# SoM-MGTH.net
KiCad netlist of a schematic drawn in Altium Designer
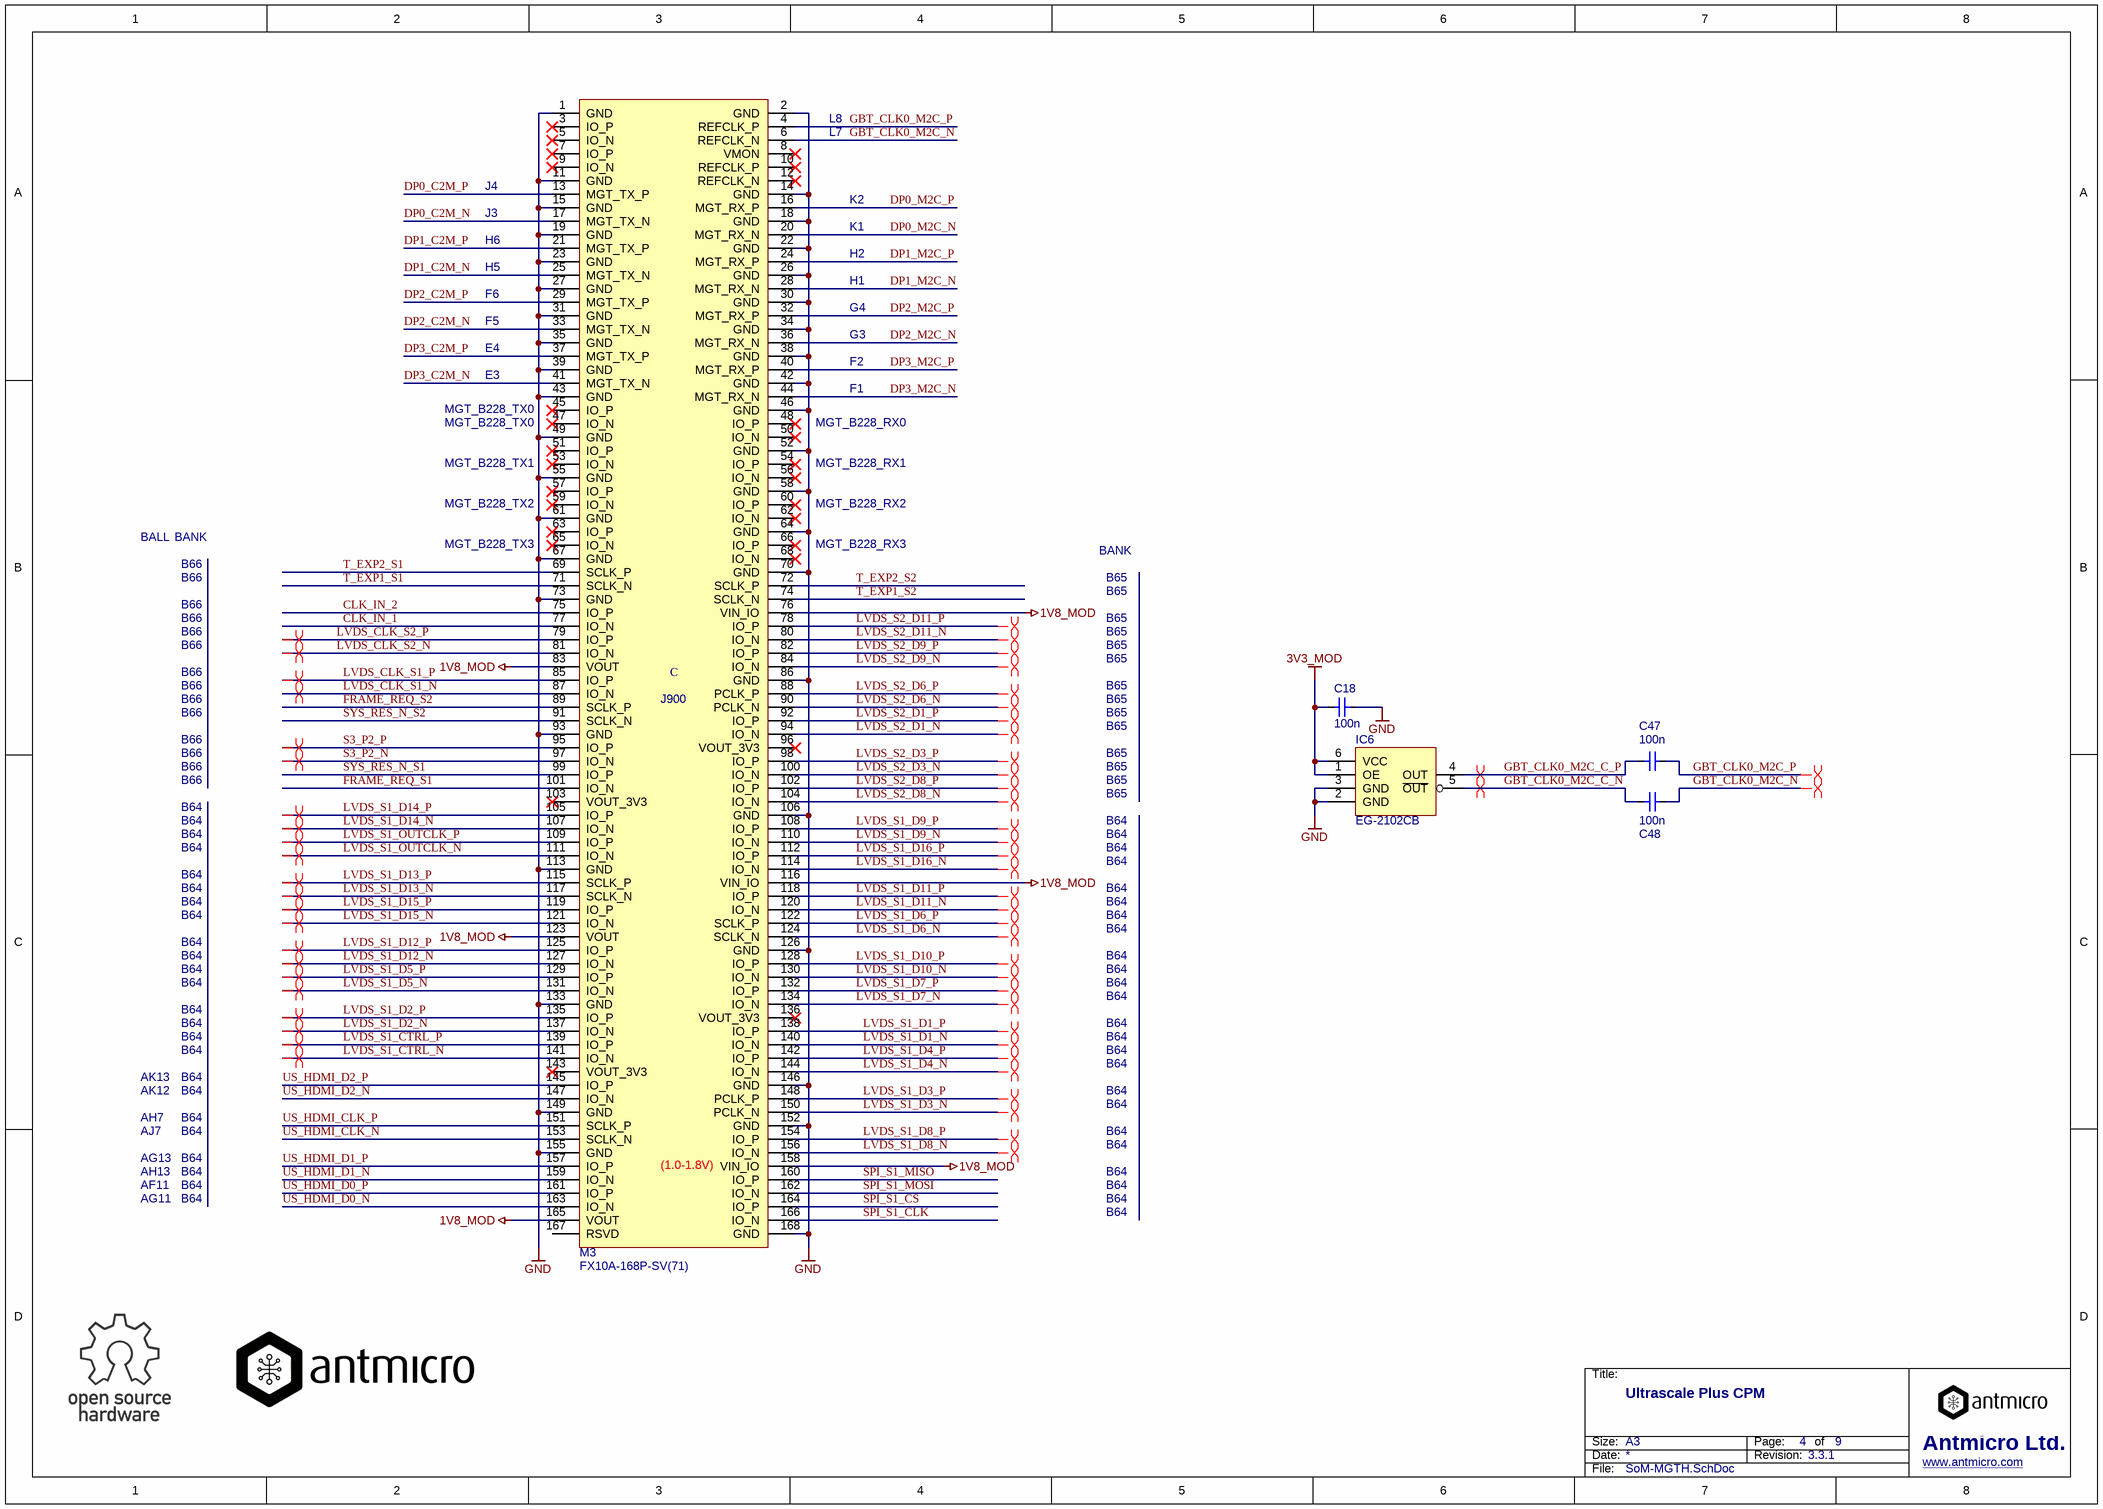
[diagram p0: SoM-MGTH.SchDoc]

(export (version "E")
  (design (tool "Eeschema 10.0.6"))
  (components
    (comp (ref "C18")
      (value "100n")
      (footprint "0402")
      (description "MLCC SMT Capacitor 100nF 0402")
      (fields (field (name "PART NUMBER") "C_100n_0402") (field (name "MANUFACTURER") "MULTICOMP"))
      (libsource (lib "US-Plus-CPM") (part "C"))
    )
    (comp (ref "C47")
      (value "100n")
      (footprint "0402")
      (description "MLCC SMT Capacitor 100nF 0402")
      (fields (field (name "PART NUMBER") "C_100n_0402") (field (name "MANUFACTURER") "MULTICOMP"))
      (libsource (lib "US-Plus-CPM") (part "C"))
    )
    (comp (ref "C48")
      (value "100n")
      (footprint "0402")
      (description "MLCC SMT Capacitor 100nF 0402")
      (fields (field (name "PART NUMBER") "C_100n_0402") (field (name "MANUFACTURER") "MULTICOMP"))
      (libsource (lib "US-Plus-CPM") (part "C"))
    )
    (comp (ref "IC6")
      (value "EG-2102CB")
      (footprint "EG-2102CB")
      (description "Standard Clock Oscillators 156.25MHz 3V3")
      (fields (field (name "MANUFACTURER") "Epson") (field (name "MPN") "EG-2102CB 156.2500M-LGPAL3"))
      (libsource (lib "US-Plus-CPM") (part "EG-2102CB"))
    )
    (comp (ref "M3")
      (value "FX10A-168P-SV(71)")
      (footprint "HIROSE_FX10A-168P-SV(71)")
      (description "Enclustra Mercury Ultrascale connector")
      (fields (field (name "PART NUMBER") "Mercury_US1_C") (field (name "MANUFACTURER") "Hirose"))
      (libsource (lib "US-Plus-CPM") (part "Mercury_US1_C"))
    )
  )
  (nets
    (net (code "1") (name "/CLK_IN_1") (class "Default")
      (node (ref "M3") (pin "77") (pinfunction "IO_N_77") (pintype "passive"))
    )
    (net (code "2") (name "/CLK_IN_2") (class "Default")
      (node (ref "M3") (pin "75") (pinfunction "IO_P_75") (pintype "passive"))
    )
    (net (code "3") (name "/DP0_C2M_N") (class "Default")
      (node (ref "M3") (pin "17") (pinfunction "MGT_TX_N_17") (pintype "passive"))
    )
    (net (code "4") (name "/DP0_C2M_P") (class "Default")
      (node (ref "M3") (pin "13") (pinfunction "MGT_TX_P_13") (pintype "passive"))
    )
    (net (code "5") (name "/DP0_M2C_N") (class "Default")
      (node (ref "M3") (pin "20") (pinfunction "MGT_RX_N_20") (pintype "passive"))
    )
    (net (code "6") (name "/DP0_M2C_P") (class "Default")
      (node (ref "M3") (pin "16") (pinfunction "MGT_RX_P_16") (pintype "passive"))
    )
    (net (code "7") (name "/DP1_C2M_N") (class "Default")
      (node (ref "M3") (pin "25") (pinfunction "MGT_TX_N_25") (pintype "passive"))
    )
    (net (code "8") (name "/DP1_C2M_P") (class "Default")
      (node (ref "M3") (pin "21") (pinfunction "MGT_TX_P_21") (pintype "passive"))
    )
    (net (code "9") (name "/DP1_M2C_N") (class "Default")
      (node (ref "M3") (pin "28") (pinfunction "MGT_RX_N_28") (pintype "passive"))
    )
    (net (code "10") (name "/DP1_M2C_P") (class "Default")
      (node (ref "M3") (pin "24") (pinfunction "MGT_RX_P_24") (pintype "passive"))
    )
    (net (code "11") (name "/DP2_C2M_N") (class "Default")
      (node (ref "M3") (pin "33") (pinfunction "MGT_TX_N_33") (pintype "passive"))
    )
    (net (code "12") (name "/DP2_C2M_P") (class "Default")
      (node (ref "M3") (pin "29") (pinfunction "MGT_TX_P_29") (pintype "passive"))
    )
    (net (code "13") (name "/DP2_M2C_N") (class "Default")
      (node (ref "M3") (pin "36") (pinfunction "MGT_RX_N_36") (pintype "passive"))
    )
    (net (code "14") (name "/DP2_M2C_P") (class "Default")
      (node (ref "M3") (pin "32") (pinfunction "MGT_RX_P_32") (pintype "passive"))
    )
    (net (code "15") (name "/DP3_C2M_N") (class "Default")
      (node (ref "M3") (pin "41") (pinfunction "MGT_TX_N_41") (pintype "passive"))
    )
    (net (code "16") (name "/DP3_C2M_P") (class "Default")
      (node (ref "M3") (pin "37") (pinfunction "MGT_TX_P_37") (pintype "passive"))
    )
    (net (code "17") (name "/DP3_M2C_N") (class "Default")
      (node (ref "M3") (pin "44") (pinfunction "MGT_RX_N_44") (pintype "passive"))
    )
    (net (code "18") (name "/DP3_M2C_P") (class "Default")
      (node (ref "M3") (pin "40") (pinfunction "MGT_RX_P_40") (pintype "passive"))
    )
    (net (code "19") (name "/FRAME_REQ_S1") (class "Default")
      (node (ref "M3") (pin "101") (pinfunction "IO_N_101") (pintype "passive"))
    )
    (net (code "20") (name "/FRAME_REQ_S2") (class "Default")
      (node (ref "M3") (pin "89") (pinfunction "SCLK_P_89") (pintype "passive"))
    )
    (net (code "21") (name "/GBT_CLK0_M2C_C_N") (class "Default")
      (node (ref "C48") (pin "1") (pinfunction "1_1") (pintype "passive"))
      (node (ref "IC6") (pin "5") (pinfunction "~{OUT}_5") (pintype "passive"))
    )
    (net (code "22") (name "/GBT_CLK0_M2C_C_P") (class "Default")
      (node (ref "C47") (pin "1") (pinfunction "1_1") (pintype "passive"))
      (node (ref "IC6") (pin "4") (pinfunction "OUT_4") (pintype "passive"))
    )
    (net (code "23") (name "/GBT_CLK0_M2C_N") (class "Default")
      (node (ref "C48") (pin "2") (pinfunction "2_2") (pintype "passive"))
      (node (ref "M3") (pin "6") (pinfunction "REFCLK_N_6") (pintype "passive"))
    )
    (net (code "24") (name "/GBT_CLK0_M2C_P") (class "Default")
      (node (ref "C47") (pin "2") (pinfunction "2_2") (pintype "passive"))
      (node (ref "M3") (pin "4") (pinfunction "REFCLK_P_4") (pintype "passive"))
    )
    (net (code "25") (name "/LVDS_CLK_S1_N") (class "Default")
      (node (ref "M3") (pin "87") (pinfunction "IO_N_87") (pintype "passive"))
    )
    (net (code "26") (name "/LVDS_CLK_S1_P") (class "Default")
      (node (ref "M3") (pin "85") (pinfunction "IO_P_85") (pintype "passive"))
    )
    (net (code "27") (name "/LVDS_CLK_S2_N") (class "Default")
      (node (ref "M3") (pin "81") (pinfunction "IO_N_81") (pintype "passive"))
    )
    (net (code "28") (name "/LVDS_CLK_S2_P") (class "Default")
      (node (ref "M3") (pin "79") (pinfunction "IO_P_79") (pintype "passive"))
    )
    (net (code "29") (name "/LVDS_S1_CTRL_N") (class "Default")
      (node (ref "M3") (pin "141") (pinfunction "IO_N_141") (pintype "passive"))
    )
    (net (code "30") (name "/LVDS_S1_CTRL_P") (class "Default")
      (node (ref "M3") (pin "139") (pinfunction "IO_P_139") (pintype "passive"))
    )
    (net (code "31") (name "/LVDS_S1_D1_N") (class "Default")
      (node (ref "M3") (pin "140") (pinfunction "IO_N_140") (pintype "passive"))
    )
    (net (code "32") (name "/LVDS_S1_D1_P") (class "Default")
      (node (ref "M3") (pin "138") (pinfunction "IO_P_138") (pintype "passive"))
    )
    (net (code "33") (name "/LVDS_S1_D2_N") (class "Default")
      (node (ref "M3") (pin "137") (pinfunction "IO_N_137") (pintype "passive"))
    )
    (net (code "34") (name "/LVDS_S1_D2_P") (class "Default")
      (node (ref "M3") (pin "135") (pinfunction "IO_P_135") (pintype "passive"))
    )
    (net (code "35") (name "/LVDS_S1_D3_N") (class "Default")
      (node (ref "M3") (pin "150") (pinfunction "PCLK_N_150") (pintype "passive"))
    )
    (net (code "36") (name "/LVDS_S1_D3_P") (class "Default")
      (node (ref "M3") (pin "148") (pinfunction "PCLK_P_148") (pintype "passive"))
    )
    (net (code "37") (name "/LVDS_S1_D4_N") (class "Default")
      (node (ref "M3") (pin "144") (pinfunction "IO_N_144") (pintype "passive"))
    )
    (net (code "38") (name "/LVDS_S1_D4_P") (class "Default")
      (node (ref "M3") (pin "142") (pinfunction "IO_P_142") (pintype "passive"))
    )
    (net (code "39") (name "/LVDS_S1_D5_N") (class "Default")
      (node (ref "M3") (pin "131") (pinfunction "IO_N_131") (pintype "passive"))
    )
    (net (code "40") (name "/LVDS_S1_D5_P") (class "Default")
      (node (ref "M3") (pin "129") (pinfunction "IO_P_129") (pintype "passive"))
    )
    (net (code "41") (name "/LVDS_S1_D6_N") (class "Default")
      (node (ref "M3") (pin "124") (pinfunction "SCLK_N_124") (pintype "passive"))
    )
    (net (code "42") (name "/LVDS_S1_D6_P") (class "Default")
      (node (ref "M3") (pin "122") (pinfunction "SCLK_P_122") (pintype "passive"))
    )
    (net (code "43") (name "/LVDS_S1_D7_N") (class "Default")
      (node (ref "M3") (pin "134") (pinfunction "IO_N_134") (pintype "passive"))
    )
    (net (code "44") (name "/LVDS_S1_D7_P") (class "Default")
      (node (ref "M3") (pin "132") (pinfunction "IO_P_132") (pintype "passive"))
    )
    (net (code "45") (name "/LVDS_S1_D8_N") (class "Default")
      (node (ref "M3") (pin "156") (pinfunction "IO_N_156") (pintype "passive"))
    )
    (net (code "46") (name "/LVDS_S1_D8_P") (class "Default")
      (node (ref "M3") (pin "154") (pinfunction "IO_P_154") (pintype "passive"))
    )
    (net (code "47") (name "/LVDS_S1_D9_N") (class "Default")
      (node (ref "M3") (pin "110") (pinfunction "IO_N_110") (pintype "passive"))
    )
    (net (code "48") (name "/LVDS_S1_D9_P") (class "Default")
      (node (ref "M3") (pin "108") (pinfunction "IO_P_108") (pintype "passive"))
    )
    (net (code "49") (name "/LVDS_S1_D10_N") (class "Default")
      (node (ref "M3") (pin "130") (pinfunction "IO_N_130") (pintype "passive"))
    )
    (net (code "50") (name "/LVDS_S1_D10_P") (class "Default")
      (node (ref "M3") (pin "128") (pinfunction "IO_P_128") (pintype "passive"))
    )
    (net (code "51") (name "/LVDS_S1_D11_N") (class "Default")
      (node (ref "M3") (pin "120") (pinfunction "IO_N_120") (pintype "passive"))
    )
    (net (code "52") (name "/LVDS_S1_D11_P") (class "Default")
      (node (ref "M3") (pin "118") (pinfunction "IO_P_118") (pintype "passive"))
    )
    (net (code "53") (name "/LVDS_S1_D12_N") (class "Default")
      (node (ref "M3") (pin "127") (pinfunction "IO_N_127") (pintype "passive"))
    )
    (net (code "54") (name "/LVDS_S1_D12_P") (class "Default")
      (node (ref "M3") (pin "125") (pinfunction "IO_P_125") (pintype "passive"))
    )
    (net (code "55") (name "/LVDS_S1_D13_N") (class "Default")
      (node (ref "M3") (pin "117") (pinfunction "SCLK_N_117") (pintype "passive"))
    )
    (net (code "56") (name "/LVDS_S1_D13_P") (class "Default")
      (node (ref "M3") (pin "115") (pinfunction "SCLK_P_115") (pintype "passive"))
    )
    (net (code "57") (name "/LVDS_S1_D14_N") (class "Default")
      (node (ref "M3") (pin "107") (pinfunction "IO_N_107") (pintype "passive"))
    )
    (net (code "58") (name "/LVDS_S1_D14_P") (class "Default")
      (node (ref "M3") (pin "105") (pinfunction "IO_P_105") (pintype "passive"))
    )
    (net (code "59") (name "/LVDS_S1_D15_N") (class "Default")
      (node (ref "M3") (pin "121") (pinfunction "IO_N_121") (pintype "passive"))
    )
    (net (code "60") (name "/LVDS_S1_D15_P") (class "Default")
      (node (ref "M3") (pin "119") (pinfunction "IO_P_119") (pintype "passive"))
    )
    (net (code "61") (name "/LVDS_S1_D16_N") (class "Default")
      (node (ref "M3") (pin "114") (pinfunction "IO_N_114") (pintype "passive"))
    )
    (net (code "62") (name "/LVDS_S1_D16_P") (class "Default")
      (node (ref "M3") (pin "112") (pinfunction "IO_P_112") (pintype "passive"))
    )
    (net (code "63") (name "/LVDS_S1_OUTCLK_N") (class "Default")
      (node (ref "M3") (pin "111") (pinfunction "IO_N_111") (pintype "passive"))
    )
    (net (code "64") (name "/LVDS_S1_OUTCLK_P") (class "Default")
      (node (ref "M3") (pin "109") (pinfunction "IO_P_109") (pintype "passive"))
    )
    (net (code "65") (name "/LVDS_S2_D1_N") (class "Default")
      (node (ref "M3") (pin "94") (pinfunction "IO_N_94") (pintype "passive"))
    )
    (net (code "66") (name "/LVDS_S2_D1_P") (class "Default")
      (node (ref "M3") (pin "92") (pinfunction "IO_P_92") (pintype "passive"))
    )
    (net (code "67") (name "/LVDS_S2_D3_N") (class "Default")
      (node (ref "M3") (pin "100") (pinfunction "IO_N_100") (pintype "passive"))
    )
    (net (code "68") (name "/LVDS_S2_D3_P") (class "Default")
      (node (ref "M3") (pin "98") (pinfunction "IO_P_98") (pintype "passive"))
    )
    (net (code "69") (name "/LVDS_S2_D6_N") (class "Default")
      (node (ref "M3") (pin "90") (pinfunction "PCLK_N_90") (pintype "passive"))
    )
    (net (code "70") (name "/LVDS_S2_D6_P") (class "Default")
      (node (ref "M3") (pin "88") (pinfunction "PCLK_P_88") (pintype "passive"))
    )
    (net (code "71") (name "/LVDS_S2_D8_N") (class "Default")
      (node (ref "M3") (pin "104") (pinfunction "IO_N_104") (pintype "passive"))
    )
    (net (code "72") (name "/LVDS_S2_D8_P") (class "Default")
      (node (ref "M3") (pin "102") (pinfunction "IO_P_102") (pintype "passive"))
    )
    (net (code "73") (name "/LVDS_S2_D9_N") (class "Default")
      (node (ref "M3") (pin "84") (pinfunction "IO_N_84") (pintype "passive"))
    )
    (net (code "74") (name "/LVDS_S2_D9_P") (class "Default")
      (node (ref "M3") (pin "82") (pinfunction "IO_P_82") (pintype "passive"))
    )
    (net (code "75") (name "/LVDS_S2_D11_N") (class "Default")
      (node (ref "M3") (pin "80") (pinfunction "IO_N_80") (pintype "passive"))
    )
    (net (code "76") (name "/LVDS_S2_D11_P") (class "Default")
      (node (ref "M3") (pin "78") (pinfunction "IO_P_78") (pintype "passive"))
    )
    (net (code "77") (name "/S3_P2_N") (class "Default")
      (node (ref "M3") (pin "97") (pinfunction "IO_N_97") (pintype "passive"))
    )
    (net (code "78") (name "/S3_P2_P") (class "Default")
      (node (ref "M3") (pin "95") (pinfunction "IO_P_95") (pintype "passive"))
    )
    (net (code "79") (name "/SPI_S1_CLK") (class "Default")
      (node (ref "M3") (pin "166") (pinfunction "IO_N_166") (pintype "passive"))
    )
    (net (code "80") (name "/SPI_S1_CS") (class "Default")
      (node (ref "M3") (pin "164") (pinfunction "IO_P_164") (pintype "passive"))
    )
    (net (code "81") (name "/SPI_S1_MISO") (class "Default")
      (node (ref "M3") (pin "160") (pinfunction "IO_P_160") (pintype "passive"))
    )
    (net (code "82") (name "/SPI_S1_MOSI") (class "Default")
      (node (ref "M3") (pin "162") (pinfunction "IO_N_162") (pintype "passive"))
    )
    (net (code "83") (name "/SYS_RES_N_S1") (class "Default")
      (node (ref "M3") (pin "99") (pinfunction "IO_P_99") (pintype "passive"))
    )
    (net (code "84") (name "/SYS_RES_N_S2") (class "Default")
      (node (ref "M3") (pin "91") (pinfunction "SCLK_N_91") (pintype "passive"))
    )
    (net (code "85") (name "/T_EXP1_S1") (class "Default")
      (node (ref "M3") (pin "71") (pinfunction "SCLK_N_71") (pintype "passive"))
    )
    (net (code "86") (name "/T_EXP1_S2") (class "Default")
      (node (ref "M3") (pin "74") (pinfunction "SCLK_N_74") (pintype "passive"))
    )
    (net (code "87") (name "/T_EXP2_S1") (class "Default")
      (node (ref "M3") (pin "69") (pinfunction "SCLK_P_69") (pintype "passive"))
    )
    (net (code "88") (name "/T_EXP2_S2") (class "Default")
      (node (ref "M3") (pin "72") (pinfunction "SCLK_P_72") (pintype "passive"))
    )
    (net (code "89") (name "/US_HDMI_CLK_N") (class "Default")
      (node (ref "M3") (pin "153") (pinfunction "SCLK_N_153") (pintype "passive"))
    )
    (net (code "90") (name "/US_HDMI_CLK_P") (class "Default")
      (node (ref "M3") (pin "151") (pinfunction "SCLK_P_151") (pintype "passive"))
    )
    (net (code "91") (name "/US_HDMI_D0_N") (class "Default")
      (node (ref "M3") (pin "163") (pinfunction "IO_N_163") (pintype "passive"))
    )
    (net (code "92") (name "/US_HDMI_D0_P") (class "Default")
      (node (ref "M3") (pin "161") (pinfunction "IO_P_161") (pintype "passive"))
    )
    (net (code "93") (name "/US_HDMI_D1_N") (class "Default")
      (node (ref "M3") (pin "159") (pinfunction "IO_N_159") (pintype "passive"))
    )
    (net (code "94") (name "/US_HDMI_D1_P") (class "Default")
      (node (ref "M3") (pin "157") (pinfunction "IO_P_157") (pintype "passive"))
    )
    (net (code "95") (name "/US_HDMI_D2_N") (class "Default")
      (node (ref "M3") (pin "147") (pinfunction "IO_N_147") (pintype "passive"))
    )
    (net (code "96") (name "/US_HDMI_D2_P") (class "Default")
      (node (ref "M3") (pin "145") (pinfunction "IO_P_145") (pintype "passive"))
    )
    (net (code "97") (name "1V8_MOD") (class "Default")
      (node (ref "M3") (pin "116") (pinfunction "VIN_IO_116") (pintype "passive"))
      (node (ref "M3") (pin "123") (pinfunction "VOUT_123") (pintype "passive"))
      (node (ref "M3") (pin "158") (pinfunction "VIN_IO_158") (pintype "passive"))
      (node (ref "M3") (pin "165") (pinfunction "VOUT_165") (pintype "passive"))
      (node (ref "M3") (pin "76") (pinfunction "VIN_IO_76") (pintype "passive"))
      (node (ref "M3") (pin "83") (pinfunction "VOUT_83") (pintype "passive"))
    )
    (net (code "98") (name "3V3_MOD") (class "Default")
      (node (ref "C18") (pin "2") (pinfunction "2_2") (pintype "passive"))
      (node (ref "IC6") (pin "1") (pinfunction "OE_1") (pintype "passive"))
      (node (ref "IC6") (pin "6") (pinfunction "VCC_6") (pintype "passive"))
    )
    (net (code "99") (name "GND") (class "Default")
      (node (ref "C18") (pin "1") (pinfunction "1_1") (pintype "passive"))
      (node (ref "IC6") (pin "2") (pinfunction "GND_2") (pintype "passive"))
      (node (ref "IC6") (pin "3") (pinfunction "GND_3") (pintype "passive"))
      (node (ref "M3") (pin "1") (pinfunction "GND_1") (pintype "passive"))
      (node (ref "M3") (pin "106") (pinfunction "GND_106") (pintype "passive"))
      (node (ref "M3") (pin "11") (pinfunction "GND_11") (pintype "passive"))
      (node (ref "M3") (pin "113") (pinfunction "GND_113") (pintype "passive"))
      (node (ref "M3") (pin "126") (pinfunction "GND_126") (pintype "passive"))
      (node (ref "M3") (pin "133") (pinfunction "GND_133") (pintype "passive"))
      (node (ref "M3") (pin "14") (pinfunction "GND_14") (pintype "passive"))
      (node (ref "M3") (pin "146") (pinfunction "GND_146") (pintype "passive"))
      (node (ref "M3") (pin "149") (pinfunction "GND_149") (pintype "passive"))
      (node (ref "M3") (pin "15") (pinfunction "GND_15") (pintype "passive"))
      (node (ref "M3") (pin "152") (pinfunction "GND_152") (pintype "passive"))
      (node (ref "M3") (pin "155") (pinfunction "GND_155") (pintype "passive"))
      (node (ref "M3") (pin "168") (pinfunction "GND_168") (pintype "passive"))
      (node (ref "M3") (pin "18") (pinfunction "GND_18") (pintype "passive"))
      (node (ref "M3") (pin "19") (pinfunction "GND_19") (pintype "passive"))
      (node (ref "M3") (pin "2") (pinfunction "GND_2") (pintype "passive"))
      (node (ref "M3") (pin "22") (pinfunction "GND_22") (pintype "passive"))
      (node (ref "M3") (pin "23") (pinfunction "GND_23") (pintype "passive"))
      (node (ref "M3") (pin "26") (pinfunction "GND_26") (pintype "passive"))
      (node (ref "M3") (pin "27") (pinfunction "GND_27") (pintype "passive"))
      (node (ref "M3") (pin "30") (pinfunction "GND_30") (pintype "passive"))
      (node (ref "M3") (pin "31") (pinfunction "GND_31") (pintype "passive"))
      (node (ref "M3") (pin "34") (pinfunction "GND_34") (pintype "passive"))
      (node (ref "M3") (pin "35") (pinfunction "GND_35") (pintype "passive"))
      (node (ref "M3") (pin "38") (pinfunction "GND_38") (pintype "passive"))
      (node (ref "M3") (pin "39") (pinfunction "GND_39") (pintype "passive"))
      (node (ref "M3") (pin "42") (pinfunction "GND_42") (pintype "passive"))
      (node (ref "M3") (pin "43") (pinfunction "GND_43") (pintype "passive"))
      (node (ref "M3") (pin "46") (pinfunction "GND_46") (pintype "passive"))
      (node (ref "M3") (pin "49") (pinfunction "GND_49") (pintype "passive"))
      (node (ref "M3") (pin "52") (pinfunction "GND_52") (pintype "passive"))
      (node (ref "M3") (pin "55") (pinfunction "GND_55") (pintype "passive"))
      (node (ref "M3") (pin "58") (pinfunction "GND_58") (pintype "passive"))
      (node (ref "M3") (pin "61") (pinfunction "GND_61") (pintype "passive"))
      (node (ref "M3") (pin "64") (pinfunction "GND_64") (pintype "passive"))
      (node (ref "M3") (pin "67") (pinfunction "GND_67") (pintype "passive"))
      (node (ref "M3") (pin "70") (pinfunction "GND_70") (pintype "passive"))
      (node (ref "M3") (pin "73") (pinfunction "GND_73") (pintype "passive"))
      (node (ref "M3") (pin "86") (pinfunction "GND_86") (pintype "passive"))
      (node (ref "M3") (pin "93") (pinfunction "GND_93") (pintype "passive"))
    )
    (net (code "100") (name "unconnected-(M3-IO_N-Pad5)") (class "Default")
      (node (ref "M3") (pin "5") (pinfunction "IO_N_5") (pintype "passive+no_connect"))
    )
    (net (code "101") (name "unconnected-(M3-IO_N-Pad9)") (class "Default")
      (node (ref "M3") (pin "9") (pinfunction "IO_N_9") (pintype "passive+no_connect"))
    )
    (net (code "102") (name "unconnected-(M3-IO_N-Pad47)") (class "Default")
      (node (ref "M3") (pin "47") (pinfunction "IO_N_47") (pintype "passive+no_connect"))
    )
    (net (code "103") (name "unconnected-(M3-IO_N-Pad50)") (class "Default")
      (node (ref "M3") (pin "50") (pinfunction "IO_N_50") (pintype "passive+no_connect"))
    )
    (net (code "104") (name "unconnected-(M3-IO_N-Pad53)") (class "Default")
      (node (ref "M3") (pin "53") (pinfunction "IO_N_53") (pintype "passive+no_connect"))
    )
    (net (code "105") (name "unconnected-(M3-IO_N-Pad56)") (class "Default")
      (node (ref "M3") (pin "56") (pinfunction "IO_N_56") (pintype "passive+no_connect"))
    )
    (net (code "106") (name "unconnected-(M3-IO_N-Pad59)") (class "Default")
      (node (ref "M3") (pin "59") (pinfunction "IO_N_59") (pintype "passive+no_connect"))
    )
    (net (code "107") (name "unconnected-(M3-IO_N-Pad62)") (class "Default")
      (node (ref "M3") (pin "62") (pinfunction "IO_N_62") (pintype "passive+no_connect"))
    )
    (net (code "108") (name "unconnected-(M3-IO_N-Pad65)") (class "Default")
      (node (ref "M3") (pin "65") (pinfunction "IO_N_65") (pintype "passive+no_connect"))
    )
    (net (code "109") (name "unconnected-(M3-IO_N-Pad68)") (class "Default")
      (node (ref "M3") (pin "68") (pinfunction "IO_N_68") (pintype "passive+no_connect"))
    )
    (net (code "110") (name "unconnected-(M3-IO_P-Pad3)") (class "Default")
      (node (ref "M3") (pin "3") (pinfunction "IO_P_3") (pintype "passive+no_connect"))
    )
    (net (code "111") (name "unconnected-(M3-IO_P-Pad7)") (class "Default")
      (node (ref "M3") (pin "7") (pinfunction "IO_P_7") (pintype "passive+no_connect"))
    )
    (net (code "112") (name "unconnected-(M3-IO_P-Pad45)") (class "Default")
      (node (ref "M3") (pin "45") (pinfunction "IO_P_45") (pintype "passive+no_connect"))
    )
    (net (code "113") (name "unconnected-(M3-IO_P-Pad48)") (class "Default")
      (node (ref "M3") (pin "48") (pinfunction "IO_P_48") (pintype "passive+no_connect"))
    )
    (net (code "114") (name "unconnected-(M3-IO_P-Pad51)") (class "Default")
      (node (ref "M3") (pin "51") (pinfunction "IO_P_51") (pintype "passive+no_connect"))
    )
    (net (code "115") (name "unconnected-(M3-IO_P-Pad54)") (class "Default")
      (node (ref "M3") (pin "54") (pinfunction "IO_P_54") (pintype "passive+no_connect"))
    )
    (net (code "116") (name "unconnected-(M3-IO_P-Pad57)") (class "Default")
      (node (ref "M3") (pin "57") (pinfunction "IO_P_57") (pintype "passive+no_connect"))
    )
    (net (code "117") (name "unconnected-(M3-IO_P-Pad60)") (class "Default")
      (node (ref "M3") (pin "60") (pinfunction "IO_P_60") (pintype "passive+no_connect"))
    )
    (net (code "118") (name "unconnected-(M3-IO_P-Pad63)") (class "Default")
      (node (ref "M3") (pin "63") (pinfunction "IO_P_63") (pintype "passive+no_connect"))
    )
    (net (code "119") (name "unconnected-(M3-IO_P-Pad66)") (class "Default")
      (node (ref "M3") (pin "66") (pinfunction "IO_P_66") (pintype "passive+no_connect"))
    )
    (net (code "120") (name "unconnected-(M3-REFCLK_N-Pad12)") (class "Default")
      (node (ref "M3") (pin "12") (pinfunction "REFCLK_N_12") (pintype "passive+no_connect"))
    )
    (net (code "121") (name "unconnected-(M3-REFCLK_P-Pad10)") (class "Default")
      (node (ref "M3") (pin "10") (pinfunction "REFCLK_P_10") (pintype "passive+no_connect"))
    )
    (net (code "122") (name "unconnected-(M3-RSVD-Pad167)") (class "Default")
      (node (ref "M3") (pin "167") (pinfunction "RSVD_167") (pintype "passive"))
    )
    (net (code "123") (name "unconnected-(M3-VMON-Pad8)") (class "Default")
      (node (ref "M3") (pin "8") (pinfunction "VMON_8") (pintype "passive+no_connect"))
    )
    (net (code "124") (name "unconnected-(M3-VOUT_3V3-Pad96)") (class "Default")
      (node (ref "M3") (pin "96") (pinfunction "VOUT_3V3_96") (pintype "passive+no_connect"))
    )
    (net (code "125") (name "unconnected-(M3-VOUT_3V3-Pad103)") (class "Default")
      (node (ref "M3") (pin "103") (pinfunction "VOUT_3V3_103") (pintype "passive+no_connect"))
    )
    (net (code "126") (name "unconnected-(M3-VOUT_3V3-Pad136)") (class "Default")
      (node (ref "M3") (pin "136") (pinfunction "VOUT_3V3_136") (pintype "passive+no_connect"))
    )
    (net (code "127") (name "unconnected-(M3-VOUT_3V3-Pad143)") (class "Default")
      (node (ref "M3") (pin "143") (pinfunction "VOUT_3V3_143") (pintype "passive+no_connect"))
    )
  )
)
